# Microcontroller.net
KiCad netlist of a schematic drawn in Altium Designer
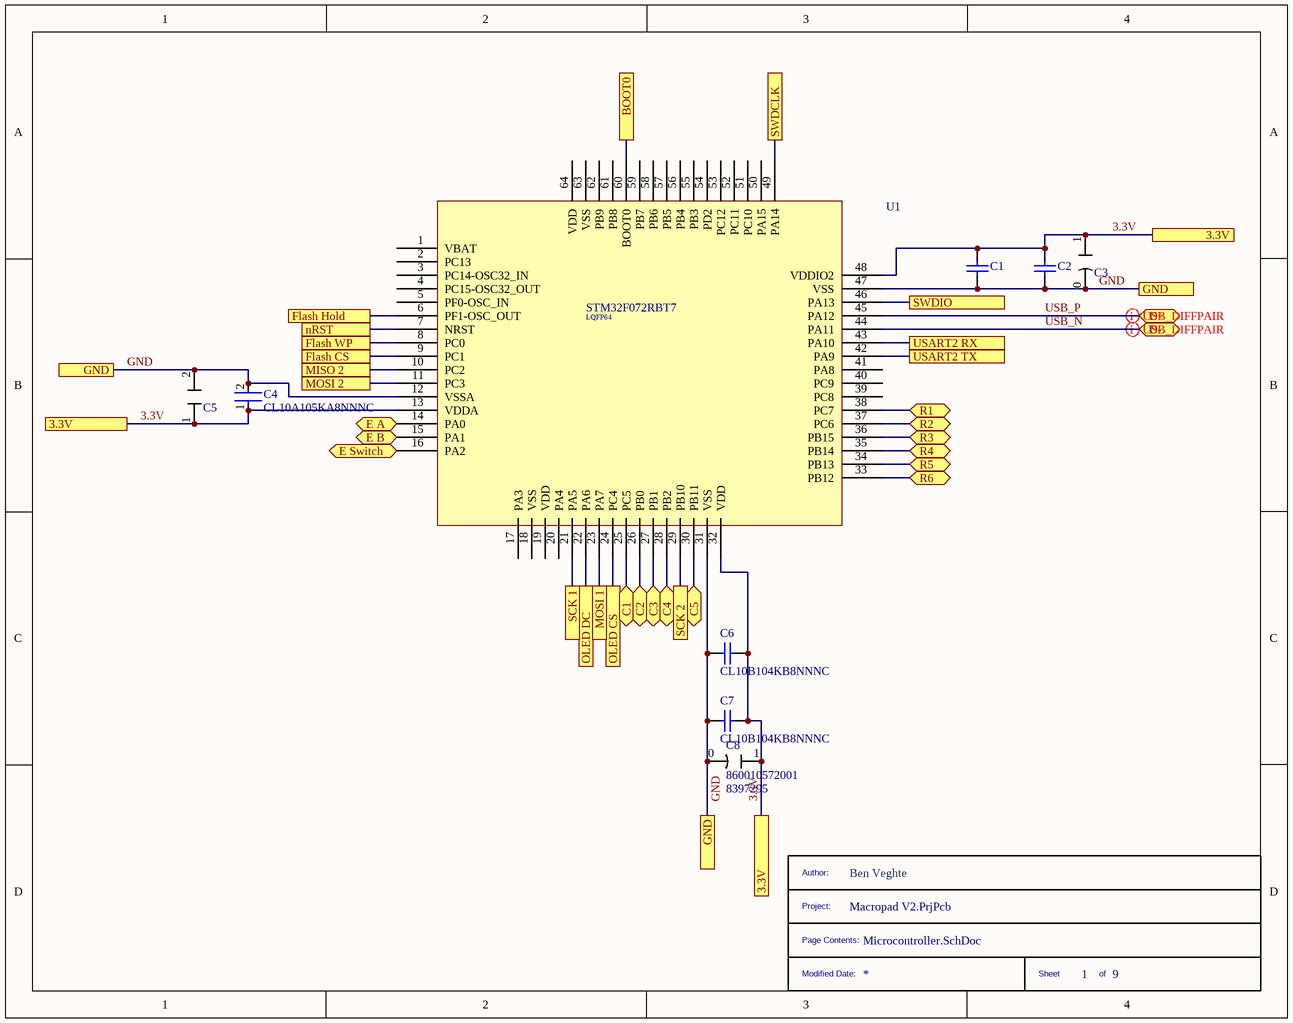
[diagram p0: Microcontroller.SchDoc]

(export (version "E")
  (design (tool "Eeschema 10.0.6"))
  (components
    (comp (ref "C1")
      (value "CL10B104KB8NNNC")
      (footprint "SAMS-C0603-2_M")
      (description "Multi-layer Ceramic Capacitor, -55 to 125 degC, 2-Pin SMD (0603), RoHS, Tape and Reel")
      (fields (field (name "MANUFACTURER") "Samsung Electro-Mechanics"))
      (libsource (lib "Altium Content Vault") (part "CAP-NP-2"))
    )
    (comp (ref "C2")
      (value "CL10B104KB8NNNC")
      (footprint "SAMS-C0603-2_M")
      (description "Multi-layer Ceramic Capacitor, -55 to 125 degC, 2-Pin SMD (0603), RoHS, Tape and Reel")
      (fields (field (name "MANUFACTURER") "Samsung Electro-Mechanics"))
      (libsource (lib "Altium Content Vault") (part "CAP-NP-2"))
    )
    (comp (ref "C3")
      (value "860010572001")
      (footprint "860010572001")
      (fields (field (name "MANUFACTURER") "Wurth Electronics") (field (name "TOLERANCE") "20%"))
      (libsource (lib "Universal Parts") (part "860010572001"))
    )
    (comp (ref "C4")
      (value "CL10A105KA8NNNC")
      (footprint "FP-CL10-IPC_C")
      (description "Cap Ceramic 1uF 25V X5R ±10% Pad SMD 0603 +85°C T/R")
      (fields (field (name "VOLTAGE") "25V") (field (name "TOLERANCE") "10%"))
      (libsource (lib "Altium Content Vault") (part "b4654b650e69147ec39a6b967a45e02"))
    )
    (comp (ref "C5")
      (value "CL10B103KB8NNNC")
      (footprint "CL10B103KB8NNNC")
      (description "CAP CER 10000PF 50V X7R 0603")
      (fields (field (name "MANUFACTURER") "Samsung") (field (name "TOLERANCE") "10%"))
      (libsource (lib "Universal Parts") (part "CL10B103KB8NNNC"))
    )
    (comp (ref "C6")
      (value "CL10B104KB8NNNC")
      (footprint "SAMS-C0603-2_M")
      (description "Multi-layer Ceramic Capacitor, -55 to 125 degC, 2-Pin SMD (0603), RoHS, Tape and Reel")
      (fields (field (name "MANUFACTURER") "Samsung Electro-Mechanics"))
      (libsource (lib "Altium Content Vault") (part "CAP-NP-2"))
    )
    (comp (ref "C7")
      (value "CL10B104KB8NNNC")
      (footprint "SAMS-C0603-2_M")
      (description "Multi-layer Ceramic Capacitor, -55 to 125 degC, 2-Pin SMD (0603), RoHS, Tape and Reel")
      (fields (field (name "MANUFACTURER") "Samsung Electro-Mechanics"))
      (libsource (lib "Altium Content Vault") (part "CAP-NP-2"))
    )
    (comp (ref "C8")
      (value "860010572001")
      (footprint "860010572001")
      (fields
        (field (name "MANUFACTURER") "Wurth Electronics")
        (field (name "TOLERANCE") "20%")
        (field (name "SUPPLIER PART NUMBER 1") "8397295")
      )
      (libsource (lib "Universal Parts") (part "860010572001"))
    )
    (comp (ref "U1")
      (value "STM32F072RBT7")
      (footprint "STM32F072RBT6")
      (description "MCU 32-Bit ARM Cortex-M0 RISC 64KB Flash 2V to 3.6V 64-Pin LQFP Tray")
      (fields (field (name "MANUFACTURER") "STMicroelectronics"))
      (libsource (lib "Universal Parts") (part "STM32F072RBT7"))
    )
  )
  (nets
    (net (code "1") (name "/3.3V") (class "Default")
      (node (ref "C1") (pin "2") (pinfunction "2_2") (pintype "passive"))
      (node (ref "C2") (pin "2") (pinfunction "2_2") (pintype "passive"))
      (node (ref "C3") (pin "1") (pinfunction "1_1") (pintype "passive"))
      (node (ref "C4") (pin "1") (pinfunction "1_1") (pintype "passive"))
      (node (ref "C5") (pin "1") (pinfunction "1_1") (pintype "passive"))
      (node (ref "C6") (pin "2") (pinfunction "2_2") (pintype "passive"))
      (node (ref "C7") (pin "2") (pinfunction "2_2") (pintype "passive"))
      (node (ref "C8") (pin "1") (pinfunction "1_1") (pintype "passive"))
      (node (ref "U1") (pin "13") (pinfunction "VDDA_13") (pintype "passive"))
      (node (ref "U1") (pin "32") (pinfunction "VDD_32") (pintype "passive"))
      (node (ref "U1") (pin "48") (pinfunction "VDDIO2_48") (pintype "passive"))
    )
    (net (code "2") (name "/BOOT0") (class "Default")
      (node (ref "U1") (pin "60") (pinfunction "BOOT0_60") (pintype "passive"))
    )
    (net (code "3") (name "/C1") (class "Default")
      (node (ref "U1") (pin "25") (pinfunction "PC5_25") (pintype "passive"))
    )
    (net (code "4") (name "/C2") (class "Default")
      (node (ref "U1") (pin "26") (pinfunction "PB0_26") (pintype "passive"))
    )
    (net (code "5") (name "/C3") (class "Default")
      (node (ref "U1") (pin "27") (pinfunction "PB1_27") (pintype "passive"))
    )
    (net (code "6") (name "/C4") (class "Default")
      (node (ref "U1") (pin "28") (pinfunction "PB2_28") (pintype "passive"))
    )
    (net (code "7") (name "/C5") (class "Default")
      (node (ref "U1") (pin "30") (pinfunction "PB11_30") (pintype "passive"))
    )
    (net (code "8") (name "/E A") (class "Default")
      (node (ref "U1") (pin "14") (pinfunction "PA0_14") (pintype "passive"))
    )
    (net (code "9") (name "/E B") (class "Default")
      (node (ref "U1") (pin "15") (pinfunction "PA1_15") (pintype "passive"))
    )
    (net (code "10") (name "/E Switch") (class "Default")
      (node (ref "U1") (pin "16") (pinfunction "PA2_16") (pintype "passive"))
    )
    (net (code "11") (name "/Flash CS") (class "Default")
      (node (ref "U1") (pin "9") (pinfunction "PC1_9") (pintype "passive"))
    )
    (net (code "12") (name "/Flash Hold") (class "Default")
      (node (ref "U1") (pin "6") (pinfunction "PF1-OSC_OUT_6") (pintype "passive"))
    )
    (net (code "13") (name "/Flash WP") (class "Default")
      (node (ref "U1") (pin "8") (pinfunction "PC0_8") (pintype "passive"))
    )
    (net (code "14") (name "/GND") (class "Default")
      (node (ref "C1") (pin "1") (pinfunction "1_1") (pintype "passive"))
      (node (ref "C2") (pin "1") (pinfunction "1_1") (pintype "passive"))
      (node (ref "C3") (pin "0") (pinfunction "0_0") (pintype "passive"))
      (node (ref "C4") (pin "2") (pinfunction "2_2") (pintype "passive"))
      (node (ref "C5") (pin "2") (pinfunction "2_2") (pintype "passive"))
      (node (ref "C6") (pin "1") (pinfunction "1_1") (pintype "passive"))
      (node (ref "C7") (pin "1") (pinfunction "1_1") (pintype "passive"))
      (node (ref "C8") (pin "0") (pinfunction "0_0") (pintype "passive"))
      (node (ref "U1") (pin "12") (pinfunction "VSSA_12") (pintype "passive"))
      (node (ref "U1") (pin "31") (pinfunction "VSS_31") (pintype "passive"))
      (node (ref "U1") (pin "47") (pinfunction "VSS_47") (pintype "passive"))
    )
    (net (code "15") (name "/MISO 2") (class "Default")
      (node (ref "U1") (pin "10") (pinfunction "PC2_10") (pintype "passive"))
    )
    (net (code "16") (name "/MOSI 1") (class "Default")
      (node (ref "U1") (pin "23") (pinfunction "PA7_23") (pintype "passive"))
    )
    (net (code "17") (name "/MOSI 2") (class "Default")
      (node (ref "U1") (pin "11") (pinfunction "PC3_11") (pintype "passive"))
    )
    (net (code "18") (name "/OLED CS") (class "Default")
      (node (ref "U1") (pin "24") (pinfunction "PC4_24") (pintype "passive"))
    )
    (net (code "19") (name "/OLED DC") (class "Default")
      (node (ref "U1") (pin "22") (pinfunction "PA6_22") (pintype "passive"))
    )
    (net (code "20") (name "/R1") (class "Default")
      (node (ref "U1") (pin "38") (pinfunction "PC7_38") (pintype "passive"))
    )
    (net (code "21") (name "/R2") (class "Default")
      (node (ref "U1") (pin "37") (pinfunction "PC6_37") (pintype "passive"))
    )
    (net (code "22") (name "/R3") (class "Default")
      (node (ref "U1") (pin "36") (pinfunction "PB15_36") (pintype "passive"))
    )
    (net (code "23") (name "/R4") (class "Default")
      (node (ref "U1") (pin "35") (pinfunction "PB14_35") (pintype "passive"))
    )
    (net (code "24") (name "/R5") (class "Default")
      (node (ref "U1") (pin "34") (pinfunction "PB13_34") (pintype "passive"))
    )
    (net (code "25") (name "/R6") (class "Default")
      (node (ref "U1") (pin "33") (pinfunction "PB12_33") (pintype "passive"))
    )
    (net (code "26") (name "/SCK 1") (class "Default")
      (node (ref "U1") (pin "21") (pinfunction "PA5_21") (pintype "passive"))
    )
    (net (code "27") (name "/SCK 2") (class "Default")
      (node (ref "U1") (pin "29") (pinfunction "PB10_29") (pintype "passive"))
    )
    (net (code "28") (name "/SWDCLK") (class "Default")
      (node (ref "U1") (pin "49") (pinfunction "PA14_49") (pintype "passive"))
    )
    (net (code "29") (name "/SWDIO") (class "Default")
      (node (ref "U1") (pin "46") (pinfunction "PA13_46") (pintype "passive"))
    )
    (net (code "30") (name "/USART2 RX") (class "Default")
      (node (ref "U1") (pin "43") (pinfunction "PA10_43") (pintype "passive"))
    )
    (net (code "31") (name "/USART2 TX") (class "Default")
      (node (ref "U1") (pin "42") (pinfunction "PA9_42") (pintype "passive"))
    )
    (net (code "32") (name "/USB_N") (class "Default")
      (node (ref "U1") (pin "44") (pinfunction "PA11_44") (pintype "passive"))
    )
    (net (code "33") (name "/USB_P") (class "Default")
      (node (ref "U1") (pin "45") (pinfunction "PA12_45") (pintype "passive"))
    )
    (net (code "34") (name "/nRST") (class "Default")
      (node (ref "U1") (pin "7") (pinfunction "NRST_7") (pintype "passive"))
    )
    (net (code "35") (name "unconnected-(U1-PA3-Pad17)") (class "Default")
      (node (ref "U1") (pin "17") (pinfunction "PA3_17") (pintype "passive"))
    )
    (net (code "36") (name "unconnected-(U1-PA4-Pad20)") (class "Default")
      (node (ref "U1") (pin "20") (pinfunction "PA4_20") (pintype "passive"))
    )
    (net (code "37") (name "unconnected-(U1-PA8-Pad41)") (class "Default")
      (node (ref "U1") (pin "41") (pinfunction "PA8_41") (pintype "passive"))
    )
    (net (code "38") (name "unconnected-(U1-PA15-Pad50)") (class "Default")
      (node (ref "U1") (pin "50") (pinfunction "PA15_50") (pintype "passive"))
    )
    (net (code "39") (name "unconnected-(U1-PB3-Pad55)") (class "Default")
      (node (ref "U1") (pin "55") (pinfunction "PB3_55") (pintype "passive"))
    )
    (net (code "40") (name "unconnected-(U1-PB4-Pad56)") (class "Default")
      (node (ref "U1") (pin "56") (pinfunction "PB4_56") (pintype "passive"))
    )
    (net (code "41") (name "unconnected-(U1-PB5-Pad57)") (class "Default")
      (node (ref "U1") (pin "57") (pinfunction "PB5_57") (pintype "passive"))
    )
    (net (code "42") (name "unconnected-(U1-PB6-Pad58)") (class "Default")
      (node (ref "U1") (pin "58") (pinfunction "PB6_58") (pintype "passive"))
    )
    (net (code "43") (name "unconnected-(U1-PB7-Pad59)") (class "Default")
      (node (ref "U1") (pin "59") (pinfunction "PB7_59") (pintype "passive"))
    )
    (net (code "44") (name "unconnected-(U1-PB8-Pad61)") (class "Default")
      (node (ref "U1") (pin "61") (pinfunction "PB8_61") (pintype "passive"))
    )
    (net (code "45") (name "unconnected-(U1-PB9-Pad62)") (class "Default")
      (node (ref "U1") (pin "62") (pinfunction "PB9_62") (pintype "passive"))
    )
    (net (code "46") (name "unconnected-(U1-PC8-Pad39)") (class "Default")
      (node (ref "U1") (pin "39") (pinfunction "PC8_39") (pintype "passive"))
    )
    (net (code "47") (name "unconnected-(U1-PC9-Pad40)") (class "Default")
      (node (ref "U1") (pin "40") (pinfunction "PC9_40") (pintype "passive"))
    )
    (net (code "48") (name "unconnected-(U1-PC10-Pad51)") (class "Default")
      (node (ref "U1") (pin "51") (pinfunction "PC10_51") (pintype "passive"))
    )
    (net (code "49") (name "unconnected-(U1-PC11-Pad52)") (class "Default")
      (node (ref "U1") (pin "52") (pinfunction "PC11_52") (pintype "passive"))
    )
    (net (code "50") (name "unconnected-(U1-PC12-Pad53)") (class "Default")
      (node (ref "U1") (pin "53") (pinfunction "PC12_53") (pintype "passive"))
    )
    (net (code "51") (name "unconnected-(U1-PC13-Pad2)") (class "Default")
      (node (ref "U1") (pin "2") (pinfunction "PC13_2") (pintype "passive"))
    )
    (net (code "52") (name "unconnected-(U1-PC14-OSC32_IN-Pad3)") (class "Default")
      (node (ref "U1") (pin "3") (pinfunction "PC14-OSC32_IN_3") (pintype "passive"))
    )
    (net (code "53") (name "unconnected-(U1-PC15-OSC32_OUT-Pad4)") (class "Default")
      (node (ref "U1") (pin "4") (pinfunction "PC15-OSC32_OUT_4") (pintype "passive"))
    )
    (net (code "54") (name "unconnected-(U1-PD2-Pad54)") (class "Default")
      (node (ref "U1") (pin "54") (pinfunction "PD2_54") (pintype "passive"))
    )
    (net (code "55") (name "unconnected-(U1-PF0-OSC_IN-Pad5)") (class "Default")
      (node (ref "U1") (pin "5") (pinfunction "PF0-OSC_IN_5") (pintype "passive"))
    )
    (net (code "56") (name "unconnected-(U1-VBAT-Pad1)") (class "Default")
      (node (ref "U1") (pin "1") (pinfunction "VBAT_1") (pintype "passive"))
    )
    (net (code "57") (name "unconnected-(U1-VDD-Pad19)") (class "Default")
      (node (ref "U1") (pin "19") (pinfunction "VDD_19") (pintype "passive"))
    )
    (net (code "58") (name "unconnected-(U1-VDD-Pad64)") (class "Default")
      (node (ref "U1") (pin "64") (pinfunction "VDD_64") (pintype "passive"))
    )
    (net (code "59") (name "unconnected-(U1-VSS-Pad18)") (class "Default")
      (node (ref "U1") (pin "18") (pinfunction "VSS_18") (pintype "passive"))
    )
    (net (code "60") (name "unconnected-(U1-VSS-Pad63)") (class "Default")
      (node (ref "U1") (pin "63") (pinfunction "VSS_63") (pintype "passive"))
    )
  )
)
